# vidaq.net
KiCad netlist of a schematic drawn in Altium Designer
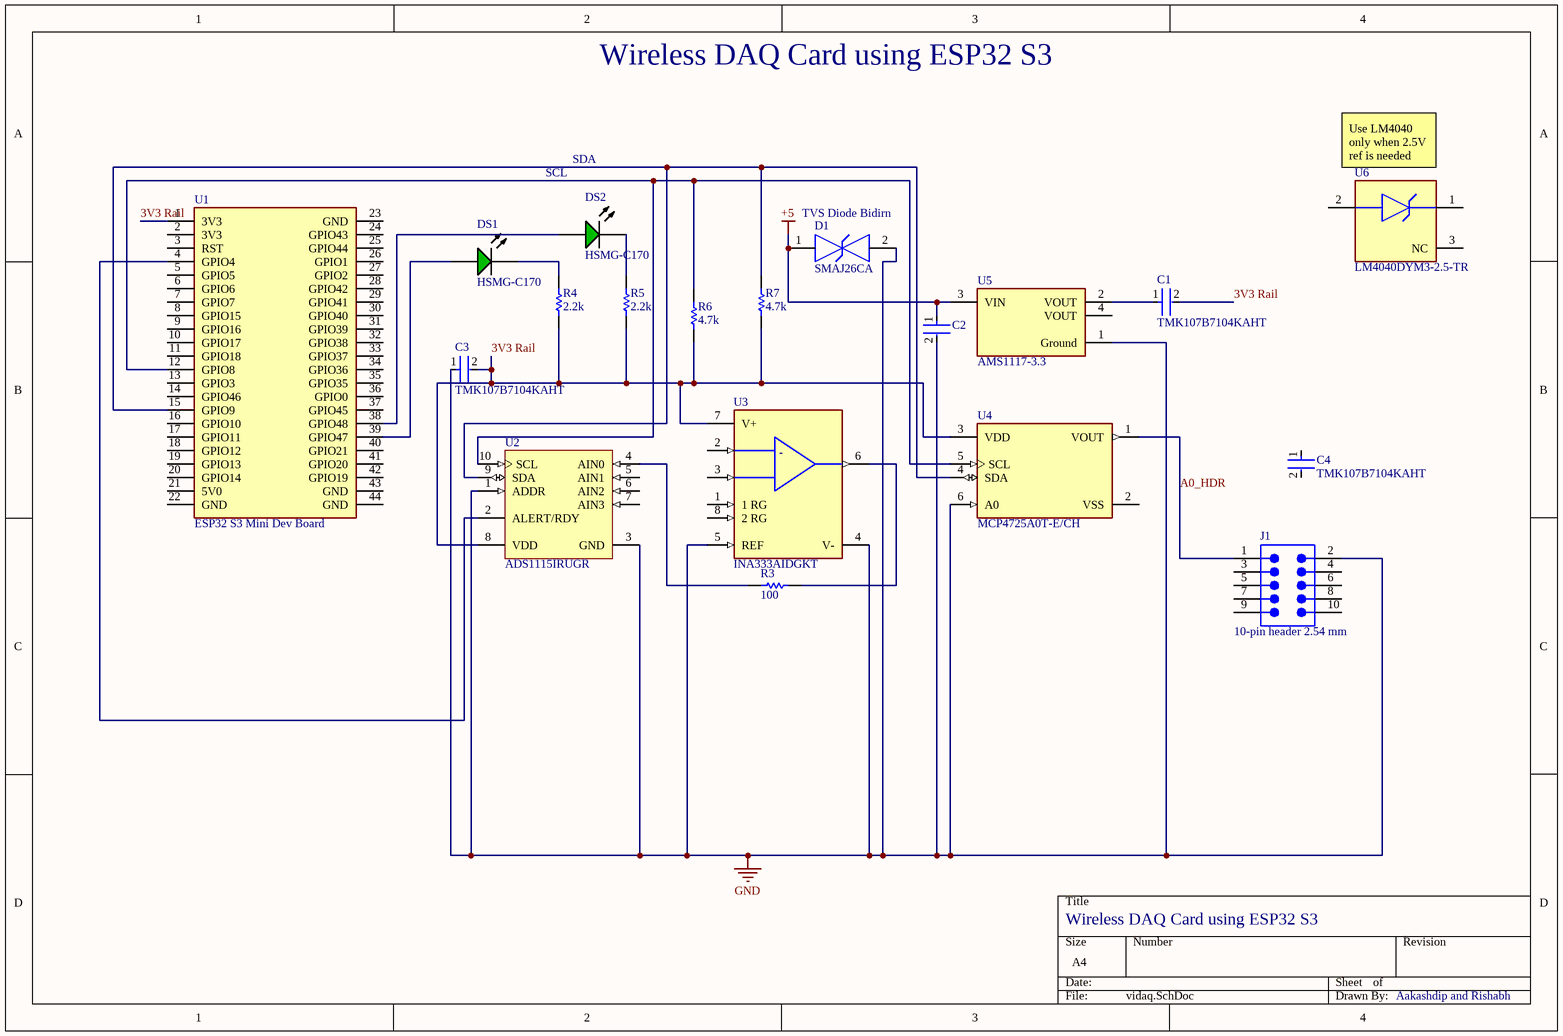
[diagram p0: vidaq.SchDoc]

(export (version "E")
  (design (tool "Eeschema 10.0.6"))
  (components
    (comp (ref "C1")
      (value "TMK107B7104KAHT")
      (footprint "FP-0603-L_1_6_0_1-W_0_8_0-IPC_C")
      (description "None")
      (fields (field (name "TOLERANCE") "10%"))
      (libsource (lib "Altium Content Vault") (part "02cd4be3c70576c341d710602a673aa"))
    )
    (comp (ref "C2")
      (value "TMK107B7104KAHT")
      (footprint "FP-0603-L_1_6_0_1-W_0_8_0-IPC_C")
      (description "None")
      (fields (field (name "TOLERANCE") "10%"))
      (libsource (lib "Altium Content Vault") (part "02cd4be3c70576c341d710602a673aa"))
    )
    (comp (ref "C3")
      (value "TMK107B7104KAHT")
      (footprint "FP-0603-L_1_6_0_1-W_0_8_0-IPC_C")
      (description "None")
      (fields (field (name "TOLERANCE") "10%"))
      (libsource (lib "Altium Content Vault") (part "02cd4be3c70576c341d710602a673aa"))
    )
    (comp (ref "C4")
      (value "TMK107B7104KAHT")
      (footprint "FP-0603-L_1_6_0_1-W_0_8_0-IPC_C")
      (description "None")
      (fields (field (name "TOLERANCE") "10%"))
      (libsource (lib "Altium Content Vault") (part "02cd4be3c70576c341d710602a673aa"))
    )
    (comp (ref "D1")
      (value "SMAJ26CA")
      (footprint "FP-SMAJ-CA-MFG")
      (description "TVS DIODE 26V 42.1V DO214AC")
      (fields
        (field (name "OCTOPART") "https://octopart.com/smaj26ca-littelfuse-350028")
        (field (name "MANUFACTURER") "Littelfuse Inc")
      )
      (libsource (lib "Altium Content Vault") (part "876f4347bf90aa6f500f43e3cd03972"))
    )
    (comp (ref "DS1")
      (value "HSMG-C170")
      (footprint "AVAG-HSMX-C170_V")
      (description "Chip LED, Green, 2.2 V, -40 to 85 degC, 2-Pin SMD, Pb-Free, Tape and Reel")
      (fields (field (name "MANUFACTURER") "Avago"))
      (libsource (lib "Altium Content Vault") (part "LED_GREEN_A1K2-2"))
    )
    (comp (ref "DS2")
      (value "HSMG-C170")
      (footprint "AVAG-HSMX-C170_V")
      (description "Chip LED, Green, 2.2 V, -40 to 85 degC, 2-Pin SMD, Pb-Free, Tape and Reel")
      (fields (field (name "MANUFACTURER") "Avago"))
      (libsource (lib "Altium Content Vault") (part "LED_GREEN_A1K2-2"))
    )
    (comp (ref "J1")
      (value "10-pin header 2.54 mm")
      (footprint "61031021121")
      (libsource (lib "Altium Content Vault") (part "Header_Male_2R_10P"))
    )
    (comp (ref "R3")
      (value "100")
      (footprint "RESC1005X40X25NL05T10")
      (description "100ohm 0402 RC0402JR-07100RL")
      (fields (field (name "PART NUMBER") "RC0402JR-07100RL") (field (name "MANUFACTURER") "Yageo / Phycomp"))
      (libsource (lib "Altium Content Vault") (part "RES"))
    )
    (comp (ref "R4")
      (value "2.2k")
      (footprint "RESC0402(1005)_N")
      (description "2K2 0.063W 5% 0402 (1005 Metric)  SMD")
      (fields (field (name "TOLERANCE") "5 %") (field (name "POWER") "0.063 W"))
      (libsource (lib "Altium Content Vault") (part "RES"))
    )
    (comp (ref "R5")
      (value "2.2k")
      (footprint "RESC0402(1005)_N")
      (description "2K2 0.063W 5% 0402 (1005 Metric)  SMD")
      (fields (field (name "TOLERANCE") "5 %") (field (name "POWER") "0.063 W"))
      (libsource (lib "Altium Content Vault") (part "RES"))
    )
    (comp (ref "R6")
      (value "4.7k")
      (footprint "RESC1210(3225)_N")
      (description "4K7 0.5W 5% 1210 (3225 Metric)  SMD")
      (fields (field (name "TOLERANCE") "5 %") (field (name "POWER") "0.5 W"))
      (libsource (lib "Altium Content Vault") (part "RES"))
    )
    (comp (ref "R7")
      (value "4.7k")
      (footprint "RESC1210(3225)_N")
      (description "4K7 0.5W 5% 1210 (3225 Metric)  SMD")
      (fields (field (name "TOLERANCE") "5 %") (field (name "POWER") "0.5 W"))
      (libsource (lib "Altium Content Vault") (part "RES"))
    )
    (comp (ref "U1")
      (value "ESP32 S3 Mini Dev Board")
      (footprint "ESP32-S3-DEVKITM-1-N8")
      (fields (field (name "DIGIKEY PART NUMBER") "1965-ESP32-S3-DEVKITM-1-N8-ND"))
      (libsource (lib "Schlib_CM5+ESP32") (part "1965-ESP32-S3-DEVKITM-1-N8-ND"))
    )
    (comp (ref "U2")
      (value "ADS1115IRUGR")
      (footprint "TI-RUG10_V")
      (fields (field (name "MANUFACTURER") "Texas Instruments"))
      (libsource (lib "Altium Content Vault") (part "TI-ADS1015_1115-10"))
    )
    (comp (ref "U3")
      (value "INA333AIDGKT")
      (footprint "FP-DGK0008A-MFG")
      (description "IC INST AMP 1 CIRCUIT 8VSSOP")
      (fields
        (field (name "MANUFACTURER") "Texas Instruments")
        (field (name "OCTOPART") "https://octopart.com/ina333aidgkt-texas+instruments-8315938")
      )
      (libsource (lib "Altium Content Vault") (part "14c63953c288e0173d78c5cf827a12c"))
    )
    (comp (ref "U4")
      (value "MCP4725A0T-E/CH")
      (footprint "FP-C04-028-CHY-IPC_A")
      (description "IC DAC 12BIT V-OUT SOT23-6")
      (libsource (lib "Altium Content Vault") (part "13d1b9b03173b6bd00baa384b893ce8"))
    )
    (comp (ref "U5")
      (value "AMS1117-3.3")
      (footprint "FP-AMS1117-IPC_C")
      (description "LDO Voltage Regulators 1A, 3.3V")
      (fields
        (field (name "OCTOPART") "https://octopart.com/ams1117-3.3-advanced+monolithic+systems-25899300")
        (field (name "MANUFACTURER") "Advanced Monolithic Systems")
      )
      (libsource (lib "Altium Content Vault") (part "8bdbb5f8e77002000e30dd2845d0354"))
    )
    (comp (ref "U6")
      (value "LM4040DYM3-2.5-TR")
      (footprint "FP-SOT23-3LD-PL-1-MFG")
      (description "IC VREF SHUNT 1% SOT23-3")
      (fields
        (field (name "OCTOPART") "https://octopart.com/lm4040dym3-2.5-tr-microchip-66800126")
        (field (name "MANUFACTURER") "Microchip")
      )
      (libsource (lib "Altium Content Vault") (part "91f0ca7be5727739b22823fb575e884"))
    )
  )
  (nets
    (net (code "1") (name "+5") (class "Default")
      (node (ref "C2") (pin "1") (pinfunction "1_1") (pintype "passive"))
      (node (ref "D1") (pin "1") (pinfunction "1_1") (pintype "passive"))
      (node (ref "U5") (pin "3") (pinfunction "VIN_3") (pintype "power_in"))
    )
    (net (code "2") (name "/3V3 Rail") (class "Default")
      (node (ref "C1") (pin "2") (pinfunction "2_2") (pintype "passive"))
      (node (ref "C3") (pin "2") (pinfunction "2_2") (pintype "passive"))
      (node (ref "R4") (pin "1") (pinfunction "1_1") (pintype "passive"))
      (node (ref "R5") (pin "1") (pinfunction "1_1") (pintype "passive"))
      (node (ref "R6") (pin "1") (pinfunction "1_1") (pintype "passive"))
      (node (ref "R7") (pin "1") (pinfunction "1_1") (pintype "passive"))
      (node (ref "U1") (pin "1") (pinfunction "3V3_1") (pintype "passive"))
      (node (ref "U2") (pin "8") (pinfunction "VDD_8") (pintype "power_in"))
      (node (ref "U3") (pin "7") (pinfunction "V+_7") (pintype "power_in"))
      (node (ref "U4") (pin "3") (pinfunction "VDD_3") (pintype "power_in"))
    )
    (net (code "3") (name "/A0_HDR") (class "Default")
      (node (ref "J1") (pin "1") (pinfunction "1_1") (pintype "passive"))
      (node (ref "U4") (pin "1") (pinfunction "VOUT_1") (pintype "output"))
    )
    (net (code "4") (name "GND") (class "Default")
      (node (ref "C2") (pin "2") (pinfunction "2_2") (pintype "passive"))
      (node (ref "C3") (pin "1") (pinfunction "1_1") (pintype "passive"))
      (node (ref "D1") (pin "2") (pinfunction "2_2") (pintype "passive"))
      (node (ref "J1") (pin "2") (pinfunction "2_2") (pintype "passive"))
      (node (ref "U2") (pin "1") (pinfunction "ADDR_1") (pintype "input"))
      (node (ref "U2") (pin "3") (pinfunction "GND_3") (pintype "power_in"))
      (node (ref "U3") (pin "4") (pinfunction "V-_4") (pintype "power_in"))
      (node (ref "U3") (pin "5") (pinfunction "REF_5") (pintype "input"))
      (node (ref "U4") (pin "6") (pinfunction "A0_6") (pintype "input"))
      (node (ref "U5") (pin "1") (pinfunction "Ground_1") (pintype "power_in"))
    )
    (net (code "5") (name "Net-(C1-Pad1)") (class "Default")
      (node (ref "C1") (pin "1") (pinfunction "1_1") (pintype "passive"))
      (node (ref "U5") (pin "2") (pinfunction "VOUT_2") (pintype "passive"))
    )
    (net (code "6") (name "Net-(DS1-A)") (class "Default")
      (node (ref "DS1") (pin "1") (pinfunction "A_1") (pintype "passive"))
      (node (ref "U1") (pin "39") (pinfunction "GPIO47_39") (pintype "passive"))
    )
    (net (code "7") (name "Net-(DS1-K)") (class "Default")
      (node (ref "DS1") (pin "2") (pinfunction "K_2") (pintype "passive"))
      (node (ref "R4") (pin "2") (pinfunction "2_2") (pintype "passive"))
    )
    (net (code "8") (name "Net-(DS2-A)") (class "Default")
      (node (ref "DS2") (pin "1") (pinfunction "A_1") (pintype "passive"))
      (node (ref "U1") (pin "38") (pinfunction "GPIO48_38") (pintype "passive"))
    )
    (net (code "9") (name "Net-(DS2-K)") (class "Default")
      (node (ref "DS2") (pin "2") (pinfunction "K_2") (pintype "passive"))
      (node (ref "R5") (pin "2") (pinfunction "2_2") (pintype "passive"))
    )
    (net (code "10") (name "Net-(U1-GPIO4)") (class "Default")
      (node (ref "U1") (pin "4") (pinfunction "GPIO4_4") (pintype "passive"))
      (node (ref "U2") (pin "2") (pinfunction "ALERT/RDY_2") (pintype "open_collector"))
    )
    (net (code "11") (name "Net-(U1-GPIO8)") (class "Default")
      (node (ref "R6") (pin "2") (pinfunction "2_2") (pintype "passive"))
      (node (ref "U1") (pin "12") (pinfunction "GPIO8_12") (pintype "passive"))
      (node (ref "U2") (pin "10") (pinfunction "SCL_10") (pintype "input"))
      (node (ref "U4") (pin "5") (pinfunction "SCL_5") (pintype "input"))
    )
    (net (code "12") (name "Net-(U1-GPIO9)") (class "Default")
      (node (ref "R7") (pin "2") (pinfunction "2_2") (pintype "passive"))
      (node (ref "U1") (pin "15") (pinfunction "GPIO9_15") (pintype "passive"))
      (node (ref "U2") (pin "9") (pinfunction "SDA_9") (pintype "bidirectional"))
      (node (ref "U4") (pin "4") (pinfunction "SDA_4") (pintype "bidirectional"))
    )
    (net (code "13") (name "Net-(U2-AIN0)") (class "Default")
      (node (ref "R3") (pin "1") (pinfunction "1_1") (pintype "passive"))
      (node (ref "U2") (pin "4") (pinfunction "AIN0_4") (pintype "input"))
    )
    (net (code "14") (name "Net-(U3-VOUT)") (class "Default")
      (node (ref "R3") (pin "2") (pinfunction "2_2") (pintype "passive"))
      (node (ref "U3") (pin "6") (pinfunction "VOUT_6") (pintype "output"))
    )
    (net (code "15") (name "unconnected-(C4-Pad1)") (class "Default")
      (node (ref "C4") (pin "1") (pinfunction "1_1") (pintype "passive"))
    )
    (net (code "16") (name "unconnected-(C4-Pad2)") (class "Default")
      (node (ref "C4") (pin "2") (pinfunction "2_2") (pintype "passive"))
    )
    (net (code "17") (name "unconnected-(J1-Pad3)") (class "Default")
      (node (ref "J1") (pin "3") (pinfunction "3_3") (pintype "passive"))
    )
    (net (code "18") (name "unconnected-(J1-Pad4)") (class "Default")
      (node (ref "J1") (pin "4") (pinfunction "4_4") (pintype "passive"))
    )
    (net (code "19") (name "unconnected-(J1-Pad5)") (class "Default")
      (node (ref "J1") (pin "5") (pinfunction "5_5") (pintype "passive"))
    )
    (net (code "20") (name "unconnected-(J1-Pad6)") (class "Default")
      (node (ref "J1") (pin "6") (pinfunction "6_6") (pintype "passive"))
    )
    (net (code "21") (name "unconnected-(J1-Pad7)") (class "Default")
      (node (ref "J1") (pin "7") (pinfunction "7_7") (pintype "passive"))
    )
    (net (code "22") (name "unconnected-(J1-Pad8)") (class "Default")
      (node (ref "J1") (pin "8") (pinfunction "8_8") (pintype "passive"))
    )
    (net (code "23") (name "unconnected-(J1-Pad9)") (class "Default")
      (node (ref "J1") (pin "9") (pinfunction "9_9") (pintype "passive"))
    )
    (net (code "24") (name "unconnected-(J1-Pad10)") (class "Default")
      (node (ref "J1") (pin "10") (pinfunction "10_10") (pintype "passive"))
    )
    (net (code "25") (name "unconnected-(U1-3V3-Pad2)") (class "Default")
      (node (ref "U1") (pin "2") (pinfunction "3V3_2") (pintype "passive"))
    )
    (net (code "26") (name "unconnected-(U1-5V0-Pad21)") (class "Default")
      (node (ref "U1") (pin "21") (pinfunction "5V0_21") (pintype "passive"))
    )
    (net (code "27") (name "unconnected-(U1-GND-Pad22)") (class "Default")
      (node (ref "U1") (pin "22") (pinfunction "GND_22") (pintype "passive"))
    )
    (net (code "28") (name "unconnected-(U1-GND-Pad23)") (class "Default")
      (node (ref "U1") (pin "23") (pinfunction "GND_23") (pintype "passive"))
    )
    (net (code "29") (name "unconnected-(U1-GND-Pad43)") (class "Default")
      (node (ref "U1") (pin "43") (pinfunction "GND_43") (pintype "passive"))
    )
    (net (code "30") (name "unconnected-(U1-GND-Pad44)") (class "Default")
      (node (ref "U1") (pin "44") (pinfunction "GND_44") (pintype "passive"))
    )
    (net (code "31") (name "unconnected-(U1-GPIO0-Pad36)") (class "Default")
      (node (ref "U1") (pin "36") (pinfunction "GPIO0_36") (pintype "passive"))
    )
    (net (code "32") (name "unconnected-(U1-GPIO1-Pad26)") (class "Default")
      (node (ref "U1") (pin "26") (pinfunction "GPIO1_26") (pintype "passive"))
    )
    (net (code "33") (name "unconnected-(U1-GPIO2-Pad27)") (class "Default")
      (node (ref "U1") (pin "27") (pinfunction "GPIO2_27") (pintype "passive"))
    )
    (net (code "34") (name "unconnected-(U1-GPIO3-Pad13)") (class "Default")
      (node (ref "U1") (pin "13") (pinfunction "GPIO3_13") (pintype "passive"))
    )
    (net (code "35") (name "unconnected-(U1-GPIO5-Pad5)") (class "Default")
      (node (ref "U1") (pin "5") (pinfunction "GPIO5_5") (pintype "passive"))
    )
    (net (code "36") (name "unconnected-(U1-GPIO6-Pad6)") (class "Default")
      (node (ref "U1") (pin "6") (pinfunction "GPIO6_6") (pintype "passive"))
    )
    (net (code "37") (name "unconnected-(U1-GPIO7-Pad7)") (class "Default")
      (node (ref "U1") (pin "7") (pinfunction "GPIO7_7") (pintype "passive"))
    )
    (net (code "38") (name "unconnected-(U1-GPIO10-Pad16)") (class "Default")
      (node (ref "U1") (pin "16") (pinfunction "GPIO10_16") (pintype "passive"))
    )
    (net (code "39") (name "unconnected-(U1-GPIO11-Pad17)") (class "Default")
      (node (ref "U1") (pin "17") (pinfunction "GPIO11_17") (pintype "passive"))
    )
    (net (code "40") (name "unconnected-(U1-GPIO12-Pad18)") (class "Default")
      (node (ref "U1") (pin "18") (pinfunction "GPIO12_18") (pintype "passive"))
    )
    (net (code "41") (name "unconnected-(U1-GPIO13-Pad19)") (class "Default")
      (node (ref "U1") (pin "19") (pinfunction "GPIO13_19") (pintype "passive"))
    )
    (net (code "42") (name "unconnected-(U1-GPIO14-Pad20)") (class "Default")
      (node (ref "U1") (pin "20") (pinfunction "GPIO14_20") (pintype "passive"))
    )
    (net (code "43") (name "unconnected-(U1-GPIO15-Pad8)") (class "Default")
      (node (ref "U1") (pin "8") (pinfunction "GPIO15_8") (pintype "passive"))
    )
    (net (code "44") (name "unconnected-(U1-GPIO16-Pad9)") (class "Default")
      (node (ref "U1") (pin "9") (pinfunction "GPIO16_9") (pintype "passive"))
    )
    (net (code "45") (name "unconnected-(U1-GPIO17-Pad10)") (class "Default")
      (node (ref "U1") (pin "10") (pinfunction "GPIO17_10") (pintype "passive"))
    )
    (net (code "46") (name "unconnected-(U1-GPIO18-Pad11)") (class "Default")
      (node (ref "U1") (pin "11") (pinfunction "GPIO18_11") (pintype "passive"))
    )
    (net (code "47") (name "unconnected-(U1-GPIO19-Pad42)") (class "Default")
      (node (ref "U1") (pin "42") (pinfunction "GPIO19_42") (pintype "passive"))
    )
    (net (code "48") (name "unconnected-(U1-GPIO20-Pad41)") (class "Default")
      (node (ref "U1") (pin "41") (pinfunction "GPIO20_41") (pintype "passive"))
    )
    (net (code "49") (name "unconnected-(U1-GPIO21-Pad40)") (class "Default")
      (node (ref "U1") (pin "40") (pinfunction "GPIO21_40") (pintype "passive"))
    )
    (net (code "50") (name "unconnected-(U1-GPIO35-Pad35)") (class "Default")
      (node (ref "U1") (pin "35") (pinfunction "GPIO35_35") (pintype "passive"))
    )
    (net (code "51") (name "unconnected-(U1-GPIO36-Pad34)") (class "Default")
      (node (ref "U1") (pin "34") (pinfunction "GPIO36_34") (pintype "passive"))
    )
    (net (code "52") (name "unconnected-(U1-GPIO37-Pad33)") (class "Default")
      (node (ref "U1") (pin "33") (pinfunction "GPIO37_33") (pintype "passive"))
    )
    (net (code "53") (name "unconnected-(U1-GPIO38-Pad32)") (class "Default")
      (node (ref "U1") (pin "32") (pinfunction "GPIO38_32") (pintype "passive"))
    )
    (net (code "54") (name "unconnected-(U1-GPIO39-Pad31)") (class "Default")
      (node (ref "U1") (pin "31") (pinfunction "GPIO39_31") (pintype "passive"))
    )
    (net (code "55") (name "unconnected-(U1-GPIO40-Pad30)") (class "Default")
      (node (ref "U1") (pin "30") (pinfunction "GPIO40_30") (pintype "passive"))
    )
    (net (code "56") (name "unconnected-(U1-GPIO41-Pad29)") (class "Default")
      (node (ref "U1") (pin "29") (pinfunction "GPIO41_29") (pintype "passive"))
    )
    (net (code "57") (name "unconnected-(U1-GPIO42-Pad28)") (class "Default")
      (node (ref "U1") (pin "28") (pinfunction "GPIO42_28") (pintype "passive"))
    )
    (net (code "58") (name "unconnected-(U1-GPIO43-Pad24)") (class "Default")
      (node (ref "U1") (pin "24") (pinfunction "GPIO43_24") (pintype "passive"))
    )
    (net (code "59") (name "unconnected-(U1-GPIO44-Pad25)") (class "Default")
      (node (ref "U1") (pin "25") (pinfunction "GPIO44_25") (pintype "passive"))
    )
    (net (code "60") (name "unconnected-(U1-GPIO45-Pad37)") (class "Default")
      (node (ref "U1") (pin "37") (pinfunction "GPIO45_37") (pintype "passive"))
    )
    (net (code "61") (name "unconnected-(U1-GPIO46-Pad14)") (class "Default")
      (node (ref "U1") (pin "14") (pinfunction "GPIO46_14") (pintype "passive"))
    )
    (net (code "62") (name "unconnected-(U1-RST-Pad3)") (class "Default")
      (node (ref "U1") (pin "3") (pinfunction "RST_3") (pintype "passive"))
    )
    (net (code "63") (name "unconnected-(U2-AIN1-Pad5)") (class "Default")
      (node (ref "U2") (pin "5") (pinfunction "AIN1_5") (pintype "input"))
    )
    (net (code "64") (name "unconnected-(U2-AIN2-Pad6)") (class "Default")
      (node (ref "U2") (pin "6") (pinfunction "AIN2_6") (pintype "input"))
    )
    (net (code "65") (name "unconnected-(U2-AIN3-Pad7)") (class "Default")
      (node (ref "U2") (pin "7") (pinfunction "AIN3_7") (pintype "input"))
    )
    (net (code "66") (name "unconnected-(U3-1_RG-Pad1)") (class "Default")
      (node (ref "U3") (pin "1") (pinfunction "1_RG_1") (pintype "input"))
    )
    (net (code "67") (name "unconnected-(U3-2_RG-Pad8)") (class "Default")
      (node (ref "U3") (pin "8") (pinfunction "2_RG_8") (pintype "input"))
    )
    (net (code "68") (name "unconnected-(U3-VIN+-Pad3)") (class "Default")
      (node (ref "U3") (pin "3") (pinfunction "VIN+_3") (pintype "input"))
    )
    (net (code "69") (name "unconnected-(U3-VIN--Pad2)") (class "Default")
      (node (ref "U3") (pin "2") (pinfunction "VIN-_2") (pintype "input"))
    )
    (net (code "70") (name "unconnected-(U4-VSS-Pad2)") (class "Default")
      (node (ref "U4") (pin "2") (pinfunction "VSS_2") (pintype "power_in"))
    )
    (net (code "71") (name "unconnected-(U5-VOUT-Pad4)") (class "Default")
      (node (ref "U5") (pin "4") (pinfunction "VOUT_4") (pintype "passive"))
    )
    (net (code "72") (name "unconnected-(U6-+-Pad1)") (class "Default")
      (node (ref "U6") (pin "1") (pinfunction "+_1") (pintype "passive"))
    )
    (net (code "73") (name "unconnected-(U6---Pad2)") (class "Default")
      (node (ref "U6") (pin "2") (pinfunction "-_2") (pintype "passive"))
    )
    (net (code "74") (name "unconnected-(U6-NC-Pad3)") (class "Default")
      (node (ref "U6") (pin "3") (pinfunction "NC_3") (pintype "passive"))
    )
  )
)
